# SCH_openELECTRO_-_ArduinoUNO_-_OVEN_2022.net
KiCad netlist of a schematic drawn in EasyEDA
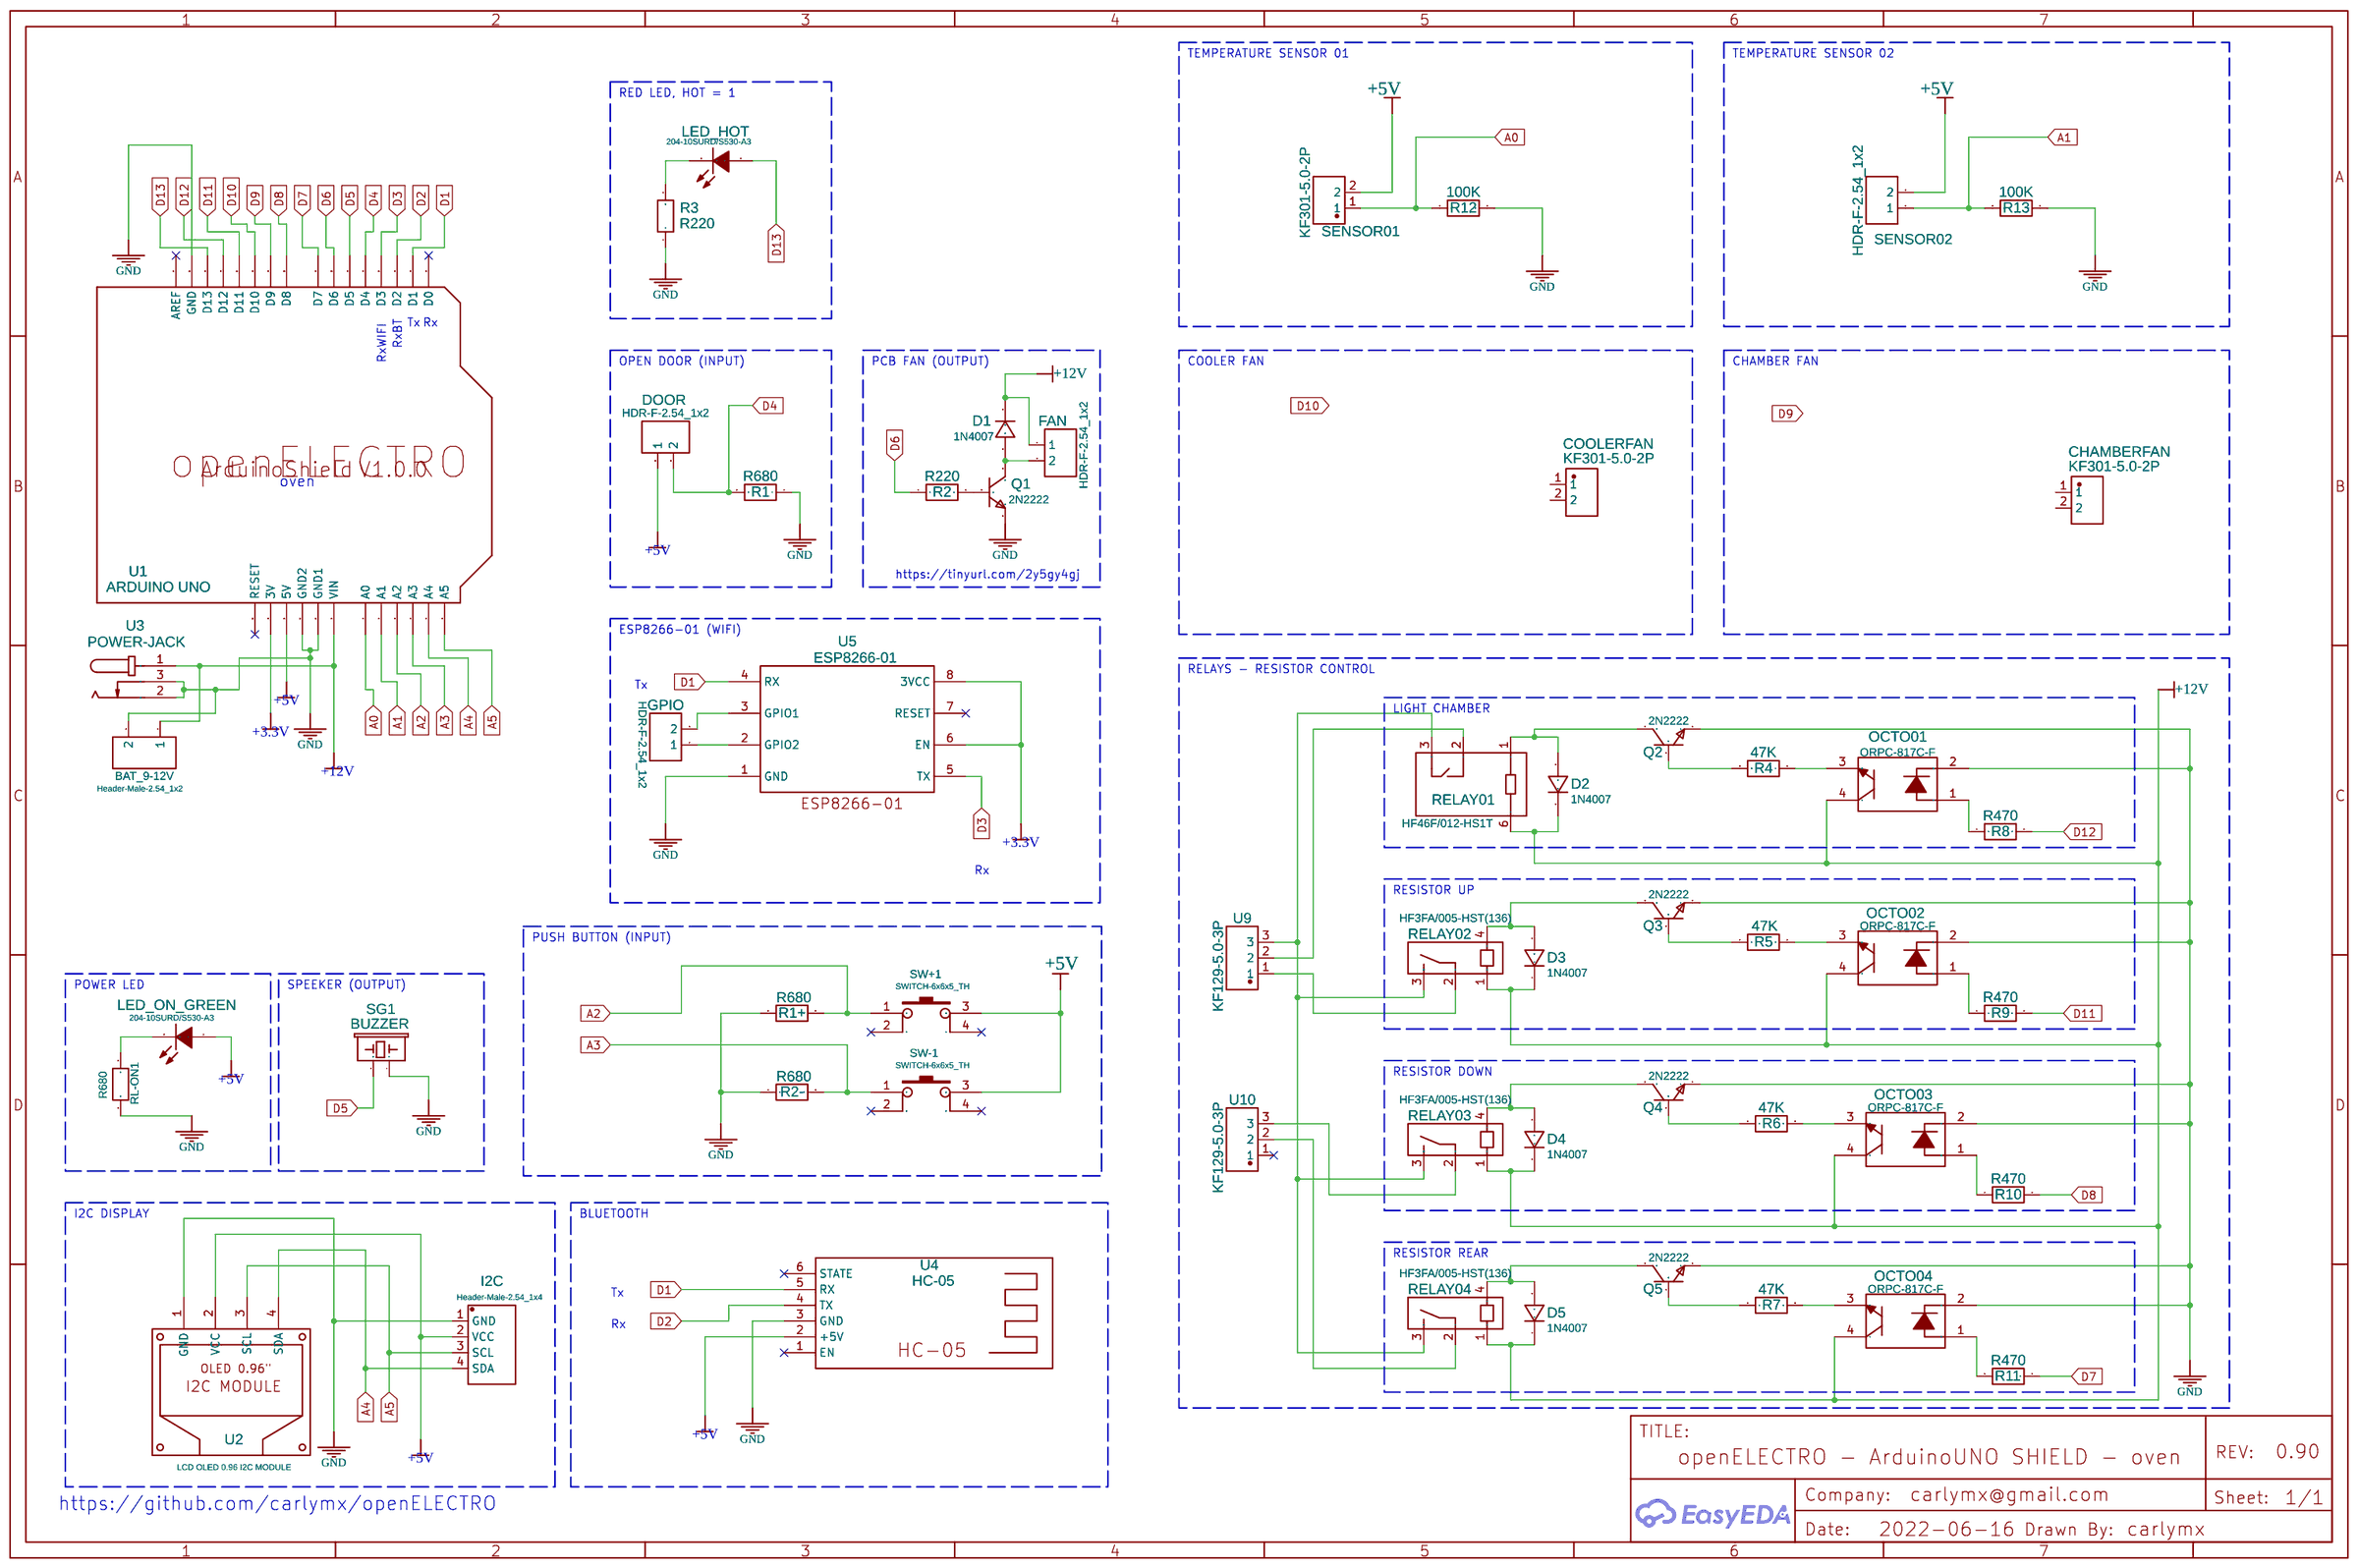
[diagram p0: schematic sheet]

(export (version "E")
  (design (tool "Eeschema 10.0.6"))
  (components
    (comp (ref "BAT_9-12V")
      (value "Header-Male-2.54_1x2")
      (fields (field (name "BOM_Manufacturer Part") "826629-2") (field (name "BOM_Supplier Part") "C86471"))
      (libsource (lib "") (part "Unknown_75_-505"))
    )
    (comp (ref "CHAMBERFAN")
      (value "KF301-5.0-2P")
      (fields (field (name "BOM_Supplier Part") "C474881"))
      (libsource (lib "") (part "KF301-5.0-2P_2"))
    )
    (comp (ref "COOLERFAN")
      (value "KF301-5.0-2P")
      (fields (field (name "BOM_Supplier Part") "C474881"))
      (libsource (lib "") (part "KF301-5.0-2P_1"))
    )
    (comp (ref "D1")
      (value "1N4007")
      (fields (field (name "BOM_Supplier Part") "C106903"))
      (libsource (lib "") (part "1N4007_1"))
    )
    (comp (ref "D2")
      (value "1N4007")
      (fields (field (name "BOM_Supplier Part") "C106903"))
      (libsource (lib "") (part "1N4007"))
    )
    (comp (ref "D3")
      (value "1N4007")
      (fields (field (name "BOM_Supplier Part") "C106903"))
      (libsource (lib "") (part "1N4007"))
    )
    (comp (ref "D4")
      (value "1N4007")
      (fields (field (name "BOM_Supplier Part") "C106903"))
      (libsource (lib "") (part "1N4007"))
    )
    (comp (ref "D5")
      (value "1N4007")
      (fields (field (name "BOM_Supplier Part") "C106903"))
      (libsource (lib "") (part "1N4007"))
    )
    (comp (ref "DOOR")
      (value "HDR-F-2.54_1x2")
      (fields (field (name "BOM_Supplier Part") "C49661"))
      (libsource (lib "") (part "HDR-F-2.54_1x2_3"))
    )
    (comp (ref "FAN")
      (value "HDR-F-2.54_1x2")
      (fields (field (name "BOM_Supplier Part") "C49661"))
      (libsource (lib "") (part "HDR-F-2.54_1x2_1"))
    )
    (comp (ref "GPIO")
      (value "HDR-F-2.54_1x2")
      (fields (field (name "BOM_Supplier Part") "C49661"))
      (libsource (lib "") (part "HDR-F-2.54_1x2"))
    )
    (comp (ref "I2C")
      (value "Header-Male-2.54_1x4")
      (fields
        (field (name "BOM_Manufacturer Part") "210S-1*4P L=11.6MMGold-plated black")
        (field (name "BOM_Supplier Part") "C124378")
      )
      (libsource (lib "") (part "Unknown_290_-125"))
    )
    (comp (ref "LED_HOT")
      (value "204-10SURD/S530-A3")
      (fields (field (name "BOM_Supplier Part") "C99772"))
      (libsource (lib "") (part "Unknown_440_-870"))
    )
    (comp (ref "LED_ON_GREEN")
      (value "204-10SURD/S530-A3")
      (fields (field (name "BOM_Supplier Part") "C99772"))
      (libsource (lib "") (part "Unknown_100_-315"))
    )
    (comp (ref "OCTO01")
      (value "ORPC-817C-F")
      (fields (field (name "BOM_Supplier Part") "C2842770"))
      (libsource (lib "") (part "ORPC-817C-F"))
    )
    (comp (ref "OCTO02")
      (value "ORPC-817C-F")
      (fields (field (name "BOM_Supplier Part") "C2842770"))
      (libsource (lib "") (part "ORPC-817C-F"))
    )
    (comp (ref "OCTO03")
      (value "ORPC-817C-F")
      (fields (field (name "BOM_Supplier Part") "C2842770"))
      (libsource (lib "") (part "ORPC-817C-F"))
    )
    (comp (ref "OCTO04")
      (value "ORPC-817C-F")
      (fields (field (name "BOM_Supplier Part") "C2842770"))
      (libsource (lib "") (part "ORPC-817C-F"))
    )
    (comp (ref "Q1")
      (value "2N2222")
      (fields (field (name "BOM_Supplier Part") "C118536"))
      (libsource (lib "") (part "2N2222_1"))
    )
    (comp (ref "Q2")
      (value "2N2222")
      (fields (field (name "BOM_Supplier Part") "C118536"))
      (libsource (lib "") (part "2N2222"))
    )
    (comp (ref "Q3")
      (value "2N2222")
      (fields (field (name "BOM_Supplier Part") "C118536"))
      (libsource (lib "") (part "2N2222"))
    )
    (comp (ref "Q4")
      (value "2N2222")
      (fields (field (name "BOM_Supplier Part") "C118536"))
      (libsource (lib "") (part "2N2222"))
    )
    (comp (ref "Q5")
      (value "2N2222")
      (fields (field (name "BOM_Supplier Part") "C118536"))
      (libsource (lib "") (part "2N2222"))
    )
    (comp (ref "R1") (value "R680") (libsource (lib "") (part "R_0603_EU_2")))
    (comp (ref "R1+") (value "R680") (libsource (lib "") (part "Res_AXIAL-0.3(1/8W)_EU")))
    (comp (ref "R2") (value "R220") (libsource (lib "") (part "R_0603_EU")))
    (comp (ref "R2-") (value "R680") (libsource (lib "") (part "Res_AXIAL-0.3(1/8W)_EU_2")))
    (comp (ref "R3") (value "R220") (libsource (lib "") (part "R_0603_EU_1")))
    (comp (ref "R4") (value "47K") (libsource (lib "") (part "R_0603_EU_2")))
    (comp (ref "R5") (value "47K") (libsource (lib "") (part "R_0603_EU")))
    (comp (ref "R6") (value "47K") (libsource (lib "") (part "R_0603_EU")))
    (comp (ref "R7") (value "47K") (libsource (lib "") (part "R_0603_EU")))
    (comp (ref "R8") (value "R470") (libsource (lib "") (part "R_0603_EU")))
    (comp (ref "R9") (value "R470") (libsource (lib "") (part "R_0603_EU")))
    (comp (ref "R10") (value "R470") (libsource (lib "") (part "R_0603_EU")))
    (comp (ref "R11") (value "R470") (libsource (lib "") (part "R_0603_EU")))
    (comp (ref "R12") (value "100K") (libsource (lib "") (part "R_0603_EU")))
    (comp (ref "R13") (value "100K") (libsource (lib "") (part "R_0603_EU")))
    (comp (ref "RELAY01")
      (value "HF46F/012-HS1T")
      (fields (field (name "BOM_Supplier Part") "C2976852"))
      (libsource (lib "") (part "HF46F/012-HS1T"))
    )
    (comp (ref "RELAY02")
      (value "HF3FA/005-HST(136)")
      (fields (field (name "BOM_Supplier Part") "C712707"))
      (libsource (lib "") (part "HF3FA/005-HST(136)"))
    )
    (comp (ref "RELAY03")
      (value "HF3FA/005-HST(136)")
      (fields (field (name "BOM_Supplier Part") "C712707"))
      (libsource (lib "") (part "HF3FA/005-HST(136)"))
    )
    (comp (ref "RELAY04")
      (value "HF3FA/005-HST(136)")
      (fields (field (name "BOM_Supplier Part") "C712707"))
      (libsource (lib "") (part "HF3FA/005-HST(136)"))
    )
    (comp (ref "RL-ON1") (value "R680") (libsource (lib "") (part "Res_AXIAL-0.3(1/8W)_EU_1")))
    (comp (ref "SENSOR01")
      (value "KF301-5.0-2P")
      (fields (field (name "BOM_Supplier Part") "C474881"))
      (libsource (lib "") (part "KF301-5.0-2P"))
    )
    (comp (ref "SENSOR02")
      (value "HDR-F-2.54_1x2")
      (fields (field (name "BOM_Supplier Part") "C49661"))
      (libsource (lib "") (part "HDR-F-2.54_1x2_2"))
    )
    (comp (ref "SG1") (value "BUZZER") (libsource (lib "") (part "Unknown_225_-305")))
    (comp (ref "SW+1")
      (value "SWITCH-6x6x5_TH")
      (fields (field (name "BOM_Supplier Part") "C69330"))
      (libsource (lib "") (part "Unknown_570_-330"))
    )
    (comp (ref "SW-1")
      (value "SWITCH-6x6x5_TH")
      (fields (field (name "BOM_Supplier Part") "C69330"))
      (libsource (lib "") (part "Unknown_570_-280"))
    )
    (comp (ref "U1") (value "ARDUINO UNO") (libsource (lib "") (part "Unknown_170_-695")))
    (comp (ref "U2")
      (value "LCD OLED 0.96 I2C MODULE")
      (fields (field (name "BOM_Manufacturer Part") "Control Chip SSD1306"))
      (libsource (lib "") (part "Unknown_80_-135"))
    )
    (comp (ref "U3")
      (value "POWER-JACK")
      (fields (field (name "BOM_Supplier Part") "C9900001795"))
      (libsource (lib "") (part "POWER-JACK"))
    )
    (comp (ref "U4") (value "HC-05") (libsource (lib "") (part "Unknown_500_-180")))
    (comp (ref "U5") (value "ESP8266-01") (libsource (lib "") (part "ESP8266-01")))
    (comp (ref "U9")
      (value "KF129-5.0-3P")
      (fields (field (name "BOM_Supplier Part") "C475091"))
      (libsource (lib "") (part "KF129-5.0-3P"))
    )
    (comp (ref "U10")
      (value "KF129-5.0-3P")
      (fields (field (name "BOM_Supplier Part") "C475091"))
      (libsource (lib "") (part "KF129-5.0-3P"))
    )
  )
  (nets
    (net (code "1") (name "+3.3V") (class "Default")
      (node (ref "U1") (pin "3V") (pinfunction "3V_3V") (pintype "passive"))
      (node (ref "U5") (pin "6") (pinfunction "EN_6") (pintype "unspecified"))
      (node (ref "U5") (pin "8") (pinfunction "3VCC_8") (pintype "unspecified"))
    )
    (net (code "2") (name "+5V") (class "Default")
      (node (ref "DOOR") (pin "1") (pinfunction "1_1") (pintype "input"))
      (node (ref "I2C") (pin "2") (pinfunction "VCC_2") (pintype "unspecified"))
      (node (ref "LED_ON_GREEN") (pin "1") (pinfunction "A_1") (pintype "unspecified"))
      (node (ref "SENSOR01") (pin "2") (pinfunction "2_2") (pintype "unspecified"))
      (node (ref "SENSOR02") (pin "2") (pinfunction "2_2") (pintype "input"))
      (node (ref "SW+1") (pin "3") (pinfunction "3_3") (pintype "input"))
      (node (ref "SW-1") (pin "3") (pinfunction "3_3") (pintype "input"))
      (node (ref "U1") (pin "5V") (pinfunction "5V_5V") (pintype "passive"))
      (node (ref "U2") (pin "2") (pinfunction "VCC_2") (pintype "unspecified"))
      (node (ref "U4") (pin "2") (pinfunction "+5V_2") (pintype "unspecified"))
    )
    (net (code "3") (name "+12V") (class "Default")
      (node (ref "BAT_9-12V") (pin "1") (pinfunction "1_1") (pintype "unspecified"))
      (node (ref "D1") (pin "1") (pinfunction "1_1") (pintype "unspecified"))
      (node (ref "D2") (pin "1") (pinfunction "1_1") (pintype "unspecified"))
      (node (ref "D3") (pin "1") (pinfunction "1_1") (pintype "unspecified"))
      (node (ref "D4") (pin "1") (pinfunction "1_1") (pintype "unspecified"))
      (node (ref "D5") (pin "1") (pinfunction "1_1") (pintype "unspecified"))
      (node (ref "FAN") (pin "1") (pinfunction "1_1") (pintype "input"))
      (node (ref "OCTO01") (pin "4") (pinfunction "4_4") (pintype "unspecified"))
      (node (ref "OCTO02") (pin "4") (pinfunction "4_4") (pintype "unspecified"))
      (node (ref "OCTO03") (pin "4") (pinfunction "4_4") (pintype "unspecified"))
      (node (ref "OCTO04") (pin "4") (pinfunction "4_4") (pintype "unspecified"))
      (node (ref "RELAY01") (pin "6") (pinfunction "6_6") (pintype "unspecified"))
      (node (ref "RELAY02") (pin "1") (pinfunction "1_1") (pintype "unspecified"))
      (node (ref "RELAY03") (pin "1") (pinfunction "1_1") (pintype "unspecified"))
      (node (ref "RELAY04") (pin "1") (pinfunction "1_1") (pintype "unspecified"))
      (node (ref "U1") (pin "VIN") (pinfunction "VIN_VIN") (pintype "passive"))
      (node (ref "U3") (pin "1") (pinfunction "1_1") (pintype "unspecified"))
    )
    (net (code "4") (name "A0") (class "Default")
      (node (ref "R12") (pin "1") (pinfunction "1_1") (pintype "unspecified"))
      (node (ref "SENSOR01") (pin "1") (pinfunction "1_1") (pintype "unspecified"))
      (node (ref "U1") (pin "A0") (pinfunction "A0_A0") (pintype "unspecified"))
    )
    (net (code "5") (name "A1") (class "Default")
      (node (ref "R13") (pin "1") (pinfunction "1_1") (pintype "unspecified"))
      (node (ref "SENSOR02") (pin "1") (pinfunction "1_1") (pintype "input"))
      (node (ref "U1") (pin "A1") (pinfunction "A1_A1") (pintype "unspecified"))
    )
    (net (code "6") (name "A2") (class "Default")
      (node (ref "R1+") (pin "2") (pinfunction "2_2") (pintype "unspecified"))
      (node (ref "SW+1") (pin "1") (pinfunction "1_1") (pintype "input"))
      (node (ref "U1") (pin "A2") (pinfunction "A2_A2") (pintype "unspecified"))
    )
    (net (code "7") (name "A3") (class "Default")
      (node (ref "R2-") (pin "2") (pinfunction "2_2") (pintype "unspecified"))
      (node (ref "SW-1") (pin "1") (pinfunction "1_1") (pintype "input"))
      (node (ref "U1") (pin "A3") (pinfunction "A3_A3") (pintype "unspecified"))
    )
    (net (code "8") (name "A4") (class "Default")
      (node (ref "I2C") (pin "4") (pinfunction "SDA_4") (pintype "unspecified"))
      (node (ref "U1") (pin "A4") (pinfunction "A4_A4") (pintype "unspecified"))
      (node (ref "U2") (pin "4") (pinfunction "SDA_4") (pintype "unspecified"))
    )
    (net (code "9") (name "A5") (class "Default")
      (node (ref "I2C") (pin "3") (pinfunction "SCL_3") (pintype "unspecified"))
      (node (ref "U1") (pin "A5") (pinfunction "A5_A5") (pintype "unspecified"))
      (node (ref "U2") (pin "3") (pinfunction "SCL_3") (pintype "unspecified"))
    )
    (net (code "10") (name "D1") (class "Default")
      (node (ref "U1") (pin "D1") (pinfunction "D1_D1") (pintype "unspecified"))
      (node (ref "U4") (pin "5") (pinfunction "RX_5") (pintype "unspecified"))
      (node (ref "U5") (pin "4") (pinfunction "RX_4") (pintype "unspecified"))
    )
    (net (code "11") (name "D2") (class "Default")
      (node (ref "U1") (pin "D2") (pinfunction "D2_D2") (pintype "unspecified"))
      (node (ref "U4") (pin "4") (pinfunction "TX_4") (pintype "unspecified"))
    )
    (net (code "12") (name "D3") (class "Default")
      (node (ref "U1") (pin "D3") (pinfunction "D3_D3") (pintype "unspecified"))
      (node (ref "U5") (pin "5") (pinfunction "TX_5") (pintype "unspecified"))
    )
    (net (code "13") (name "D4") (class "Default")
      (node (ref "DOOR") (pin "2") (pinfunction "2_2") (pintype "input"))
      (node (ref "R1") (pin "2") (pinfunction "2_2") (pintype "unspecified"))
      (node (ref "U1") (pin "D4") (pinfunction "D4_D4") (pintype "unspecified"))
    )
    (net (code "14") (name "D5") (class "Default")
      (node (ref "SG1") (pin "+") (pinfunction "1_+") (pintype "unspecified"))
      (node (ref "U1") (pin "D5") (pinfunction "D5_D5") (pintype "unspecified"))
    )
    (net (code "15") (name "D6") (class "Default")
      (node (ref "R2") (pin "1") (pinfunction "1_1") (pintype "unspecified"))
      (node (ref "U1") (pin "D6") (pinfunction "D6_D6") (pintype "unspecified"))
    )
    (net (code "16") (name "D7") (class "Default")
      (node (ref "R11") (pin "2") (pinfunction "2_2") (pintype "unspecified"))
      (node (ref "U1") (pin "D7") (pinfunction "D7_D7") (pintype "unspecified"))
    )
    (net (code "17") (name "D8") (class "Default")
      (node (ref "R10") (pin "2") (pinfunction "2_2") (pintype "unspecified"))
      (node (ref "U1") (pin "D8") (pinfunction "D8_D8") (pintype "unspecified"))
    )
    (net (code "18") (name "D9") (class "Default")
      (node (ref "U1") (pin "D9") (pinfunction "D9_D9") (pintype "unspecified"))
    )
    (net (code "19") (name "D10") (class "Default")
      (node (ref "U1") (pin "D10") (pinfunction "D10_D10") (pintype "unspecified"))
    )
    (net (code "20") (name "D11") (class "Default")
      (node (ref "R9") (pin "2") (pinfunction "2_2") (pintype "unspecified"))
      (node (ref "U1") (pin "D11") (pinfunction "D11_D11") (pintype "unspecified"))
    )
    (net (code "21") (name "D12") (class "Default")
      (node (ref "R8") (pin "2") (pinfunction "2_2") (pintype "unspecified"))
      (node (ref "U1") (pin "D12") (pinfunction "D12_D12") (pintype "unspecified"))
    )
    (net (code "22") (name "D13") (class "Default")
      (node (ref "LED_HOT") (pin "1") (pinfunction "A_1") (pintype "unspecified"))
      (node (ref "U1") (pin "D13") (pinfunction "D13_D13") (pintype "unspecified"))
    )
    (net (code "23") (name "GND") (class "Default")
      (node (ref "BAT_9-12V") (pin "2") (pinfunction "2_2") (pintype "unspecified"))
      (node (ref "I2C") (pin "1") (pinfunction "GND_1") (pintype "unspecified"))
      (node (ref "OCTO01") (pin "2") (pinfunction "2_2") (pintype "unspecified"))
      (node (ref "OCTO02") (pin "2") (pinfunction "2_2") (pintype "unspecified"))
      (node (ref "OCTO03") (pin "2") (pinfunction "2_2") (pintype "unspecified"))
      (node (ref "OCTO04") (pin "2") (pinfunction "2_2") (pintype "unspecified"))
      (node (ref "Q1") (pin "1") (pinfunction "E_1") (pintype "unspecified"))
      (node (ref "Q2") (pin "1") (pinfunction "E_1") (pintype "unspecified"))
      (node (ref "Q3") (pin "1") (pinfunction "E_1") (pintype "unspecified"))
      (node (ref "Q4") (pin "1") (pinfunction "E_1") (pintype "unspecified"))
      (node (ref "Q5") (pin "1") (pinfunction "E_1") (pintype "unspecified"))
      (node (ref "R1") (pin "1") (pinfunction "1_1") (pintype "unspecified"))
      (node (ref "R1+") (pin "1") (pinfunction "1_1") (pintype "unspecified"))
      (node (ref "R12") (pin "2") (pinfunction "2_2") (pintype "unspecified"))
      (node (ref "R13") (pin "2") (pinfunction "2_2") (pintype "unspecified"))
      (node (ref "R2-") (pin "1") (pinfunction "1_1") (pintype "unspecified"))
      (node (ref "R3") (pin "1") (pinfunction "1_1") (pintype "unspecified"))
      (node (ref "RL-ON1") (pin "1") (pinfunction "1_1") (pintype "unspecified"))
      (node (ref "SG1") (pin "-") (pinfunction "2_-") (pintype "unspecified"))
      (node (ref "U1") (pin "GND") (pinfunction "GND_GND") (pintype "passive"))
      (node (ref "U1") (pin "GND1") (pinfunction "GND1_GND1") (pintype "passive"))
      (node (ref "U1") (pin "GND2") (pinfunction "GND2_GND2") (pintype "passive"))
      (node (ref "U2") (pin "1") (pinfunction "GND_1") (pintype "unspecified"))
      (node (ref "U3") (pin "2") (pinfunction "2_2") (pintype "unspecified"))
      (node (ref "U3") (pin "3") (pinfunction "3_3") (pintype "unspecified"))
      (node (ref "U4") (pin "3") (pinfunction "GND_3") (pintype "unspecified"))
      (node (ref "U5") (pin "1") (pinfunction "GND_1") (pintype "unspecified"))
    )
    (net (code "24") (name "Net-(LED_HOT-K)") (class "Default")
      (node (ref "LED_HOT") (pin "2") (pinfunction "K_2") (pintype "unspecified"))
      (node (ref "R3") (pin "2") (pinfunction "2_2") (pintype "unspecified"))
    )
    (net (code "25") (name "Net-(LED_ON_GREEN-K)") (class "Default")
      (node (ref "LED_ON_GREEN") (pin "2") (pinfunction "K_2") (pintype "unspecified"))
      (node (ref "RL-ON1") (pin "2") (pinfunction "2_2") (pintype "unspecified"))
    )
    (net (code "26") (name "Net-(OCTO01-Pad1)") (class "Default")
      (node (ref "OCTO01") (pin "1") (pinfunction "1_1") (pintype "unspecified"))
      (node (ref "R8") (pin "1") (pinfunction "1_1") (pintype "unspecified"))
    )
    (net (code "27") (name "Net-(OCTO01-Pad3)") (class "Default")
      (node (ref "OCTO01") (pin "3") (pinfunction "3_3") (pintype "unspecified"))
      (node (ref "R4") (pin "1") (pinfunction "1_1") (pintype "unspecified"))
    )
    (net (code "28") (name "Net-(OCTO02-Pad1)") (class "Default")
      (node (ref "OCTO02") (pin "1") (pinfunction "1_1") (pintype "unspecified"))
      (node (ref "R9") (pin "1") (pinfunction "1_1") (pintype "unspecified"))
    )
    (net (code "29") (name "Net-(OCTO02-Pad3)") (class "Default")
      (node (ref "OCTO02") (pin "3") (pinfunction "3_3") (pintype "unspecified"))
      (node (ref "R5") (pin "2") (pinfunction "2_2") (pintype "unspecified"))
    )
    (net (code "30") (name "Net-(OCTO03-Pad1)") (class "Default")
      (node (ref "OCTO03") (pin "1") (pinfunction "1_1") (pintype "unspecified"))
      (node (ref "R10") (pin "1") (pinfunction "1_1") (pintype "unspecified"))
    )
    (net (code "31") (name "Net-(OCTO03-Pad3)") (class "Default")
      (node (ref "OCTO03") (pin "3") (pinfunction "3_3") (pintype "unspecified"))
      (node (ref "R6") (pin "2") (pinfunction "2_2") (pintype "unspecified"))
    )
    (net (code "32") (name "Net-(OCTO04-Pad1)") (class "Default")
      (node (ref "OCTO04") (pin "1") (pinfunction "1_1") (pintype "unspecified"))
      (node (ref "R11") (pin "1") (pinfunction "1_1") (pintype "unspecified"))
    )
    (net (code "33") (name "Net-(OCTO04-Pad3)") (class "Default")
      (node (ref "OCTO04") (pin "3") (pinfunction "3_3") (pintype "unspecified"))
      (node (ref "R7") (pin "2") (pinfunction "2_2") (pintype "unspecified"))
    )
    (net (code "34") (name "Net-(Q1-B)") (class "Default")
      (node (ref "Q1") (pin "2") (pinfunction "B_2") (pintype "unspecified"))
      (node (ref "R2") (pin "2") (pinfunction "2_2") (pintype "unspecified"))
    )
    (net (code "35") (name "Net-(Q1-C)") (class "Default")
      (node (ref "D1") (pin "2") (pinfunction "2_2") (pintype "unspecified"))
      (node (ref "FAN") (pin "2") (pinfunction "2_2") (pintype "input"))
      (node (ref "Q1") (pin "3") (pinfunction "C_3") (pintype "unspecified"))
    )
    (net (code "36") (name "Net-(Q2-B)") (class "Default")
      (node (ref "Q2") (pin "2") (pinfunction "B_2") (pintype "unspecified"))
      (node (ref "R4") (pin "2") (pinfunction "2_2") (pintype "unspecified"))
    )
    (net (code "37") (name "Net-(Q2-C)") (class "Default")
      (node (ref "D2") (pin "2") (pinfunction "2_2") (pintype "unspecified"))
      (node (ref "Q2") (pin "3") (pinfunction "C_3") (pintype "unspecified"))
      (node (ref "RELAY01") (pin "1") (pinfunction "1_1") (pintype "unspecified"))
    )
    (net (code "38") (name "Net-(Q3-B)") (class "Default")
      (node (ref "Q3") (pin "2") (pinfunction "B_2") (pintype "unspecified"))
      (node (ref "R5") (pin "1") (pinfunction "1_1") (pintype "unspecified"))
    )
    (net (code "39") (name "Net-(Q3-C)") (class "Default")
      (node (ref "D3") (pin "2") (pinfunction "2_2") (pintype "unspecified"))
      (node (ref "Q3") (pin "3") (pinfunction "C_3") (pintype "unspecified"))
      (node (ref "RELAY02") (pin "4") (pinfunction "4_4") (pintype "unspecified"))
    )
    (net (code "40") (name "Net-(Q4-B)") (class "Default")
      (node (ref "Q4") (pin "2") (pinfunction "B_2") (pintype "unspecified"))
      (node (ref "R6") (pin "1") (pinfunction "1_1") (pintype "unspecified"))
    )
    (net (code "41") (name "Net-(Q4-C)") (class "Default")
      (node (ref "D4") (pin "2") (pinfunction "2_2") (pintype "unspecified"))
      (node (ref "Q4") (pin "3") (pinfunction "C_3") (pintype "unspecified"))
      (node (ref "RELAY03") (pin "4") (pinfunction "4_4") (pintype "unspecified"))
    )
    (net (code "42") (name "Net-(Q5-B)") (class "Default")
      (node (ref "Q5") (pin "2") (pinfunction "B_2") (pintype "unspecified"))
      (node (ref "R7") (pin "1") (pinfunction "1_1") (pintype "unspecified"))
    )
    (net (code "43") (name "Net-(Q5-C)") (class "Default")
      (node (ref "D5") (pin "2") (pinfunction "2_2") (pintype "unspecified"))
      (node (ref "Q5") (pin "3") (pinfunction "C_3") (pintype "unspecified"))
      (node (ref "RELAY04") (pin "4") (pinfunction "4_4") (pintype "unspecified"))
    )
    (net (code "44") (name "Net-(RELAY01-Pad2)") (class "Default")
      (node (ref "RELAY01") (pin "2") (pinfunction "2_2") (pintype "unspecified"))
      (node (ref "U9") (pin "2") (pinfunction "2_2") (pintype "unspecified"))
    )
    (net (code "45") (name "Net-(RELAY01-Pad3)") (class "Default")
      (node (ref "RELAY01") (pin "3") (pinfunction "3_3") (pintype "unspecified"))
      (node (ref "RELAY02") (pin "3") (pinfunction "3_3") (pintype "unspecified"))
      (node (ref "RELAY03") (pin "3") (pinfunction "3_3") (pintype "unspecified"))
      (node (ref "RELAY04") (pin "3") (pinfunction "3_3") (pintype "unspecified"))
      (node (ref "U9") (pin "3") (pinfunction "3_3") (pintype "unspecified"))
    )
    (net (code "46") (name "Net-(RELAY02-Pad2)") (class "Default")
      (node (ref "RELAY02") (pin "2") (pinfunction "2_2") (pintype "unspecified"))
      (node (ref "U9") (pin "1") (pinfunction "1_1") (pintype "unspecified"))
    )
    (net (code "47") (name "Net-(RELAY03-Pad2)") (class "Default")
      (node (ref "RELAY03") (pin "2") (pinfunction "2_2") (pintype "unspecified"))
      (node (ref "U10") (pin "3") (pinfunction "3_3") (pintype "unspecified"))
    )
    (net (code "48") (name "Net-(RELAY04-Pad2)") (class "Default")
      (node (ref "RELAY04") (pin "2") (pinfunction "2_2") (pintype "unspecified"))
      (node (ref "U10") (pin "2") (pinfunction "2_2") (pintype "unspecified"))
    )
    (net (code "49") (name "Net-(U5-GPIO1)") (class "Default")
      (node (ref "GPIO") (pin "2") (pinfunction "2_2") (pintype "input"))
      (node (ref "U5") (pin "3") (pinfunction "GPIO1_3") (pintype "unspecified"))
    )
    (net (code "50") (name "Net-(U5-GPIO2)") (class "Default")
      (node (ref "GPIO") (pin "1") (pinfunction "1_1") (pintype "input"))
      (node (ref "U5") (pin "2") (pinfunction "GPIO2_2") (pintype "unspecified"))
    )
    (net (code "51") (name "unconnected-(CHAMBERFAN-Pad1)") (class "Default")
      (node (ref "CHAMBERFAN") (pin "1") (pinfunction "1_1") (pintype "unspecified"))
    )
    (net (code "52") (name "unconnected-(CHAMBERFAN-Pad2)") (class "Default")
      (node (ref "CHAMBERFAN") (pin "2") (pinfunction "2_2") (pintype "unspecified"))
    )
    (net (code "53") (name "unconnected-(COOLERFAN-Pad1)") (class "Default")
      (node (ref "COOLERFAN") (pin "1") (pinfunction "1_1") (pintype "unspecified"))
    )
    (net (code "54") (name "unconnected-(COOLERFAN-Pad2)") (class "Default")
      (node (ref "COOLERFAN") (pin "2") (pinfunction "2_2") (pintype "unspecified"))
    )
    (net (code "55") (name "unconnected-(SW+1-Pad2)") (class "Default")
      (node (ref "SW+1") (pin "2") (pinfunction "2_2") (pintype "input+no_connect"))
    )
    (net (code "56") (name "unconnected-(SW+1-Pad4)") (class "Default")
      (node (ref "SW+1") (pin "4") (pinfunction "4_4") (pintype "input+no_connect"))
    )
    (net (code "57") (name "unconnected-(SW-1-Pad2)") (class "Default")
      (node (ref "SW-1") (pin "2") (pinfunction "2_2") (pintype "input+no_connect"))
    )
    (net (code "58") (name "unconnected-(SW-1-Pad4)") (class "Default")
      (node (ref "SW-1") (pin "4") (pinfunction "4_4") (pintype "input+no_connect"))
    )
    (net (code "59") (name "unconnected-(U1-PadAREF)") (class "Default")
      (node (ref "U1") (pin "AREF") (pinfunction "AREF_AREF") (pintype "unspecified+no_connect"))
    )
    (net (code "60") (name "unconnected-(U1-PadD0)") (class "Default")
      (node (ref "U1") (pin "D0") (pinfunction "D0_D0") (pintype "unspecified+no_connect"))
    )
    (net (code "61") (name "unconnected-(U1-PadRESET)") (class "Default")
      (node (ref "U1") (pin "RESET") (pinfunction "RESET_RESET") (pintype "unspecified+no_connect"))
    )
    (net (code "62") (name "unconnected-(U4-EN-Pad1)") (class "Default")
      (node (ref "U4") (pin "1") (pinfunction "EN_1") (pintype "unspecified+no_connect"))
    )
    (net (code "63") (name "unconnected-(U4-STATE-Pad6)") (class "Default")
      (node (ref "U4") (pin "6") (pinfunction "STATE_6") (pintype "unspecified+no_connect"))
    )
    (net (code "64") (name "unconnected-(U5-RESET-Pad7)") (class "Default")
      (node (ref "U5") (pin "7") (pinfunction "RESET_7") (pintype "unspecified+no_connect"))
    )
    (net (code "65") (name "unconnected-(U10-Pad1)") (class "Default")
      (node (ref "U10") (pin "1") (pinfunction "1_1") (pintype "unspecified+no_connect"))
    )
  )
)
